# Main.net
KiCad netlist of a schematic drawn in Altium Designer
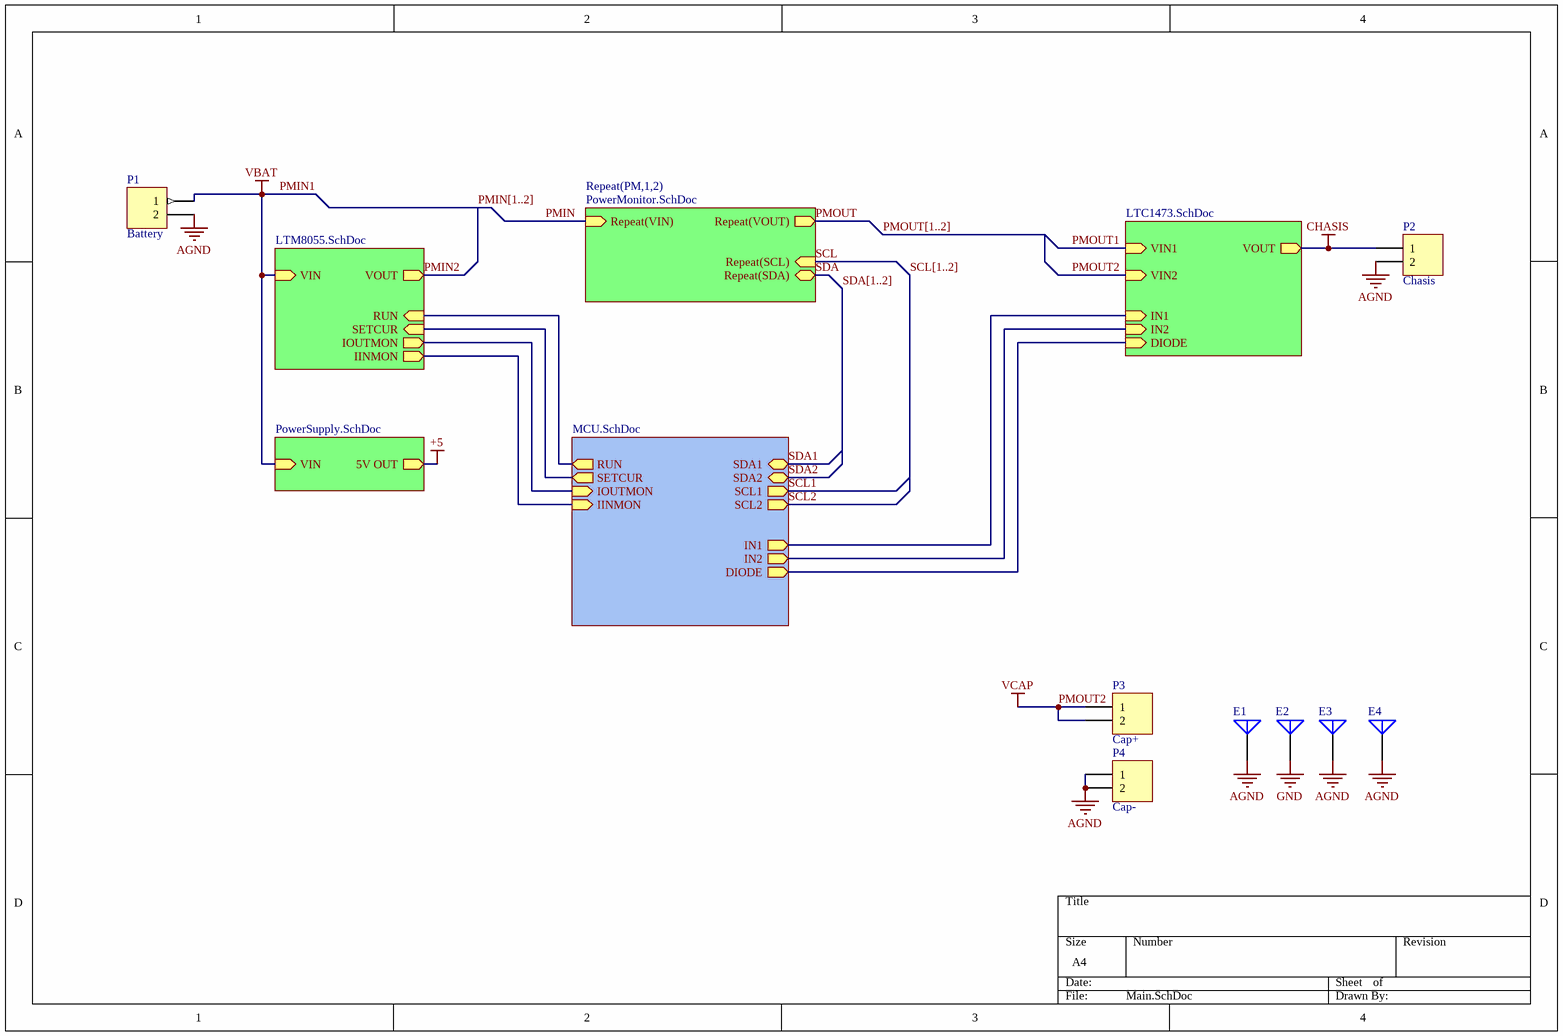
[diagram p0: Main.SchDoc]

(export (version "E")
  (design (tool "Eeschema 10.0.6"))
  (components
    (comp (ref "E1")
      (value "螺丝孔")
      (footprint "M3x4_N")
      (description "M3螺丝孔")
      (fields (field (name "PUBLISHER") "Altium Limited"))
      (libsource (lib "Miscellaneous Devices") (part "Antenna"))
    )
    (comp (ref "E2")
      (value "螺丝孔")
      (footprint "M3x4_N")
      (description "M3螺丝孔")
      (fields (field (name "PUBLISHER") "Altium Limited"))
      (libsource (lib "Miscellaneous Devices") (part "Antenna"))
    )
    (comp (ref "E3")
      (value "螺丝孔")
      (footprint "M3x4_N")
      (description "M3螺丝孔")
      (fields (field (name "PUBLISHER") "Altium Limited"))
      (libsource (lib "Miscellaneous Devices") (part "Antenna"))
    )
    (comp (ref "E4")
      (value "螺丝孔")
      (footprint "M3x4_N")
      (description "M3螺丝孔")
      (fields (field (name "PUBLISHER") "Altium Limited"))
      (libsource (lib "Miscellaneous Devices") (part "Antenna"))
    )
    (comp (ref "P1")
      (value "Battery")
      (footprint "TX60PW-M20")
      (description "XT电源接口")
      (fields (field (name "PUBLISHER") "Altium Limited"))
      (libsource (lib "") (part "Header 2_1"))
    )
    (comp (ref "P2")
      (value "Chasis")
      (footprint "TX60PW-F20")
      (description "XT电源接口")
      (fields (field (name "PUBLISHER") "Altium Limited"))
      (libsource (lib "Miscellaneous Connectors") (part "Header 2"))
    )
    (comp (ref "P3")
      (value "Cap+")
      (footprint "XT30PW-F")
      (description "XT电源接口")
      (fields (field (name "PUBLISHER") "Altium Limited"))
      (libsource (lib "Miscellaneous Connectors") (part "Header 2"))
    )
    (comp (ref "P4")
      (value "Cap-")
      (footprint "XT30U-M")
      (description "XT电源接口")
      (fields (field (name "PUBLISHER") "Altium Limited"))
      (libsource (lib "Miscellaneous Connectors") (part "Header 2"))
    )
  )
  (nets
    (net (code "23") (name "AGND") (class "Default")
      (node (ref "E1") (pin "1") (pinfunction "A_1") (pintype "passive"))
      (node (ref "E3") (pin "1") (pinfunction "A_1") (pintype "passive"))
      (node (ref "E4") (pin "1") (pinfunction "A_1") (pintype "passive"))
      (node (ref "P1") (pin "2") (pinfunction "2_2") (pintype "passive"))
      (node (ref "P2") (pin "2") (pinfunction "2_2") (pintype "passive"))
      (node (ref "P4") (pin "1") (pinfunction "1_1") (pintype "passive"))
      (node (ref "P4") (pin "2") (pinfunction "2_2") (pintype "passive"))
    )
    (net (code "24") (name "CHASIS") (class "Default")
      (node (ref "P2") (pin "1") (pinfunction "1_1") (pintype "passive"))
    )
    (net (code "25") (name "GND") (class "Default")
      (node (ref "E2") (pin "1") (pinfunction "A_1") (pintype "passive"))
    )
    (net (code "26") (name "VBAT") (class "Default")
      (node (ref "P1") (pin "1") (pinfunction "1_1") (pintype "output"))
    )
    (net (code "27") (name "VCAP") (class "Default")
      (node (ref "P3") (pin "1") (pinfunction "1_1") (pintype "passive"))
      (node (ref "P3") (pin "2") (pinfunction "2_2") (pintype "passive"))
    )
  )
)
